# Sheet4.net
KiCad netlist of a schematic drawn in Altium Designer
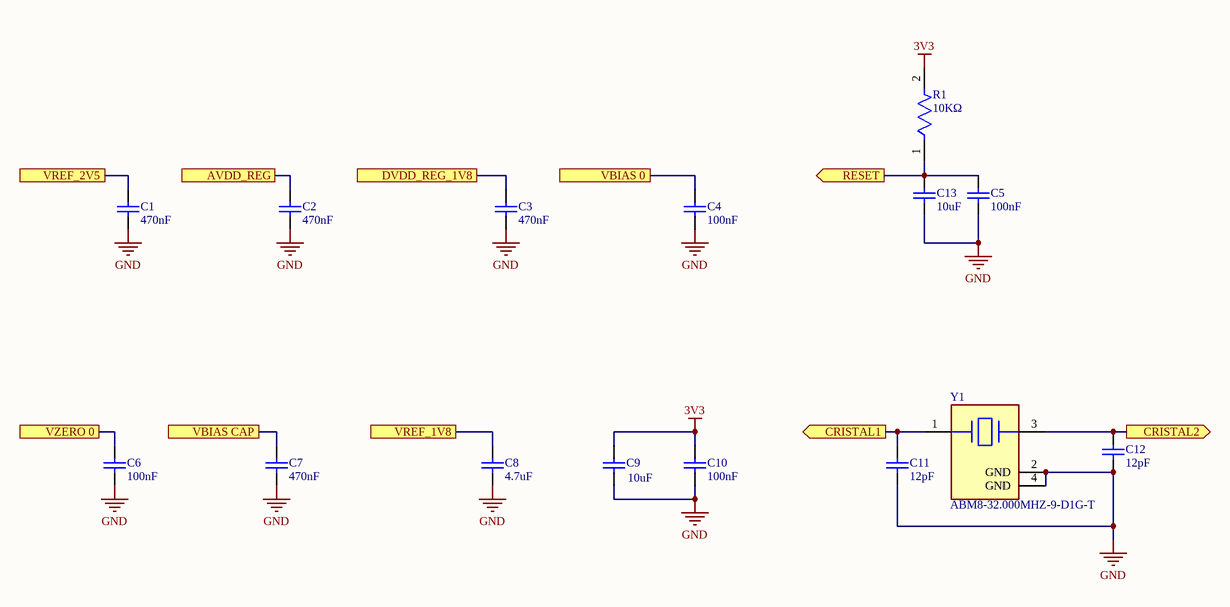
[diagram p0: Sheet4.SchDoc]

(export (version "E")
  (design (tool "Eeschema 10.0.6"))
  (components
    (comp (ref "C1")
      (value "470nF")
      (footprint "CAPC1608X95X40LL15T15")
      (fields (field (name "MANUFACTURER") "Vitramon") (field (name "PART NUMBER") "VJ0603G474KXQPW1BC"))
      (libsource (lib "Altium Content Vault") (part "CAP"))
    )
    (comp (ref "C2")
      (value "470nF")
      (footprint "CAPC1608X95X40LL15T15")
      (fields (field (name "MANUFACTURER") "Vitramon") (field (name "PART NUMBER") "VJ0603G474KXQPW1BC"))
      (libsource (lib "Altium Content Vault") (part "CAP"))
    )
    (comp (ref "C3")
      (value "470nF")
      (footprint "CAPC1608X95X40LL15T15")
      (fields (field (name "MANUFACTURER") "Vitramon") (field (name "PART NUMBER") "VJ0603G474KXQPW1BC"))
      (libsource (lib "Altium Content Vault") (part "CAP"))
    )
    (comp (ref "C4")
      (value "100nF")
      (footprint "CAPC1608X95X40LL15T15")
      (fields (field (name "MANUFACTURER") "Vitramon") (field (name "PART NUMBER") "VJ0603G474KXQPW1BC"))
      (libsource (lib "Altium Content Vault") (part "CAP"))
    )
    (comp (ref "C5")
      (value "100nF")
      (footprint "CAPC1608X95X40LL15T15")
      (fields (field (name "MANUFACTURER") "Vitramon") (field (name "PART NUMBER") "VJ0603G474KXQPW1BC"))
      (libsource (lib "Altium Content Vault") (part "CAP"))
    )
    (comp (ref "C6")
      (value "100nF")
      (footprint "CAPC1608X95X40LL15T15")
      (fields (field (name "MANUFACTURER") "Vitramon") (field (name "PART NUMBER") "VJ0603G474KXQPW1BC"))
      (libsource (lib "Altium Content Vault") (part "CAP"))
    )
    (comp (ref "C7")
      (value "470nF")
      (footprint "CAPC1608X95X40LL15T15")
      (fields (field (name "MANUFACTURER") "Vitramon") (field (name "PART NUMBER") "VJ0603G474KXQPW1BC"))
      (libsource (lib "Altium Content Vault") (part "CAP"))
    )
    (comp (ref "C8")
      (value "4.7uF")
      (footprint "CAPC1608X95X40LL15T15")
      (fields (field (name "MANUFACTURER") "Vitramon") (field (name "PART NUMBER") "VJ0603G474KXQPW1BC"))
      (libsource (lib "Altium Content Vault") (part "CAP"))
    )
    (comp (ref "C9")
      (value "10uF")
      (footprint "CAPC1608X95X40LL15T15")
      (fields (field (name "MANUFACTURER") "Vitramon") (field (name "PART NUMBER") "VJ0603G474KXQPW1BC"))
      (libsource (lib "Altium Content Vault") (part "CAP"))
    )
    (comp (ref "C10")
      (value "100nF")
      (footprint "CAPC1608X95X40LL15T15")
      (fields (field (name "MANUFACTURER") "Vitramon") (field (name "PART NUMBER") "VJ0603G474KXQPW1BC"))
      (libsource (lib "Altium Content Vault") (part "CAP"))
    )
    (comp (ref "C11")
      (value "12pF")
      (footprint "CAPC0805(2012)100_L")
      (fields (field (name "TOLERANCE") "Â±10%"))
      (libsource (lib "Altium Content Vault") (part "CAP"))
    )
    (comp (ref "C12")
      (value "12pF")
      (footprint "CAPC0805(2012)100_L")
      (fields (field (name "TOLERANCE") "Â±10%"))
      (libsource (lib "Altium Content Vault") (part "CAP"))
    )
    (comp (ref "C13")
      (value "10uF")
      (footprint "CAPC1608X95X40LL15T15")
      (fields (field (name "MANUFACTURER") "Vitramon") (field (name "PART NUMBER") "VJ0603G474KXQPW1BC"))
      (libsource (lib "Altium Content Vault") (part "CAP"))
    )
    (comp (ref "R1")
      (value "10KΩ")
      (footprint "FP-CPF0603-MFG")
      (fields
        (field (name "OCTOPART") "https://octopart.com/cpf0603d10ke-te+connectivity-22737789")
        (field (name "MANUFACTURER") "TE Connectivity")
        (field (name "TOLERANCE") "0.5%")
      )
      (libsource (lib "Altium Content Vault") (part "1029c3af85768c4190bb7ad29bc67b5"))
    )
    (comp (ref "Y1")
      (value "ABM8-32.000MHZ-9-D1G-T")
      (footprint "FP-ABM8-MFG")
      (description "Crystal 32MHz ±10ppm 9pF SMD-4 3.2mm x 2.5mm")
      (libsource (lib "Altium Content Vault") (part "dfdb7f9a12507849fb681da9a70121c"))
    )
  )
  (nets
    (net (code "1") (name "/AVDD_REG") (class "Default")
      (node (ref "C2") (pin "2") (pinfunction "2_2") (pintype "passive"))
    )
    (net (code "2") (name "/CRISTAL1") (class "Default")
      (node (ref "C11") (pin "1") (pinfunction "1_1") (pintype "passive"))
      (node (ref "Y1") (pin "1") (pinfunction "1_1") (pintype "passive"))
    )
    (net (code "3") (name "/CRISTAL2") (class "Default")
      (node (ref "C12") (pin "1") (pinfunction "1_1") (pintype "passive"))
      (node (ref "Y1") (pin "3") (pinfunction "3_3") (pintype "passive"))
    )
    (net (code "4") (name "/DVDD_REG_1V8") (class "Default")
      (node (ref "C3") (pin "2") (pinfunction "2_2") (pintype "passive"))
    )
    (net (code "5") (name "/RESET") (class "Default")
      (node (ref "C13") (pin "2") (pinfunction "2_2") (pintype "passive"))
      (node (ref "C5") (pin "2") (pinfunction "2_2") (pintype "passive"))
      (node (ref "R1") (pin "1") (pinfunction "1_1") (pintype "passive"))
    )
    (net (code "6") (name "/VBIAS 0") (class "Default")
      (node (ref "C4") (pin "2") (pinfunction "2_2") (pintype "passive"))
    )
    (net (code "7") (name "/VBIAS CAP") (class "Default")
      (node (ref "C7") (pin "2") (pinfunction "2_2") (pintype "passive"))
    )
    (net (code "8") (name "/VREF_1V8") (class "Default")
      (node (ref "C8") (pin "2") (pinfunction "2_2") (pintype "passive"))
    )
    (net (code "9") (name "/VREF_2V5") (class "Default")
      (node (ref "C1") (pin "2") (pinfunction "2_2") (pintype "passive"))
    )
    (net (code "10") (name "/VZERO 0") (class "Default")
      (node (ref "C6") (pin "2") (pinfunction "2_2") (pintype "passive"))
    )
    (net (code "11") (name "3V3") (class "Default")
      (node (ref "C10") (pin "2") (pinfunction "2_2") (pintype "passive"))
      (node (ref "C9") (pin "2") (pinfunction "2_2") (pintype "passive"))
      (node (ref "R1") (pin "2") (pinfunction "2_2") (pintype "passive"))
    )
    (net (code "12") (name "GND") (class "Default")
      (node (ref "C1") (pin "1") (pinfunction "1_1") (pintype "passive"))
      (node (ref "C10") (pin "1") (pinfunction "1_1") (pintype "passive"))
      (node (ref "C11") (pin "2") (pinfunction "2_2") (pintype "passive"))
      (node (ref "C12") (pin "2") (pinfunction "2_2") (pintype "passive"))
      (node (ref "C13") (pin "1") (pinfunction "1_1") (pintype "passive"))
      (node (ref "C2") (pin "1") (pinfunction "1_1") (pintype "passive"))
      (node (ref "C3") (pin "1") (pinfunction "1_1") (pintype "passive"))
      (node (ref "C4") (pin "1") (pinfunction "1_1") (pintype "passive"))
      (node (ref "C5") (pin "1") (pinfunction "1_1") (pintype "passive"))
      (node (ref "C6") (pin "1") (pinfunction "1_1") (pintype "passive"))
      (node (ref "C7") (pin "1") (pinfunction "1_1") (pintype "passive"))
      (node (ref "C8") (pin "1") (pinfunction "1_1") (pintype "passive"))
      (node (ref "C9") (pin "1") (pinfunction "1_1") (pintype "passive"))
      (node (ref "Y1") (pin "2") (pinfunction "GND_2") (pintype "power_in"))
      (node (ref "Y1") (pin "4") (pinfunction "GND_4") (pintype "power_in"))
    )
  )
)
